# SLAYER_Sensors.net
KiCad netlist of a schematic drawn in Altium Designer
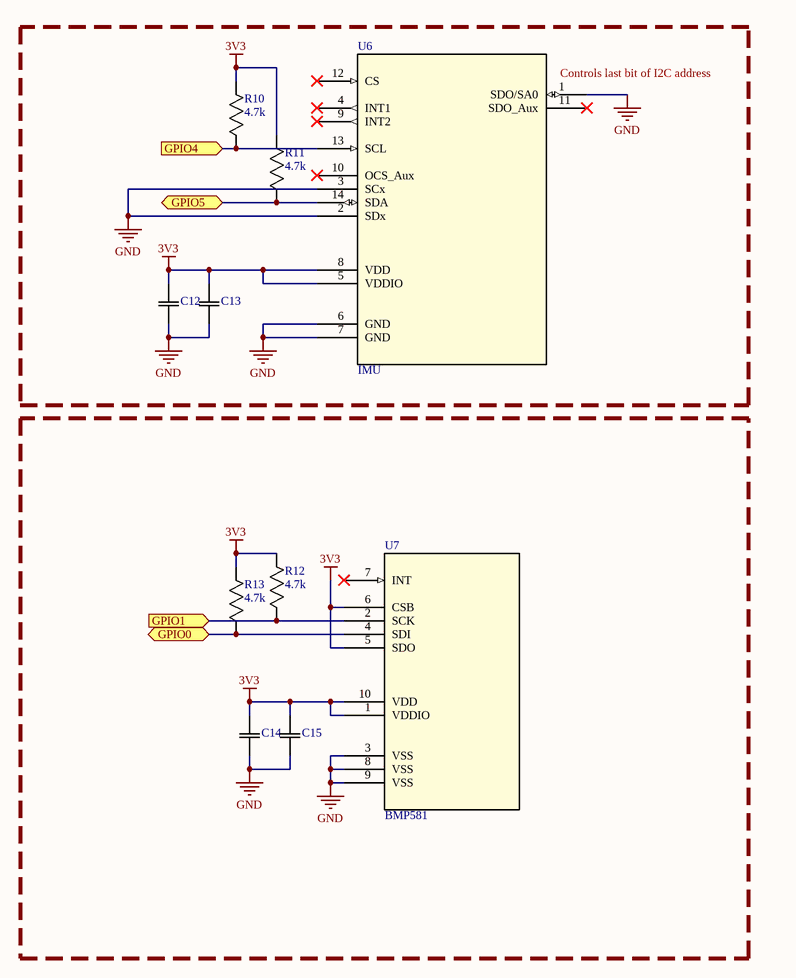
[diagram p0: SLAYER_Sensors.SchDoc]

(export (version "E")
  (design (tool "Eeschema 10.0.6"))
  (components
    (comp (ref "C12")
      (value "CC0603KRX7R9BB104")
      (footprint "0.1uF/50V")
      (fields (field (name "COPYRIGHT") "Copyright (C) 2025 Ultra Librarian. All rights reserved."))
      (libsource (lib "SLAYER_Altium_Sch") (part "0.1uF/50V"))
    )
    (comp (ref "C13")
      (value "CC0603KRX7R9BB104")
      (footprint "0.1uF/50V")
      (fields (field (name "COPYRIGHT") "Copyright (C) 2025 Ultra Librarian. All rights reserved."))
      (libsource (lib "SLAYER_Altium_Sch") (part "0.1uF/50V"))
    )
    (comp (ref "C14")
      (value "CC0603KRX7R9BB104")
      (footprint "0.1uF/50V")
      (fields (field (name "COPYRIGHT") "Copyright (C) 2025 Ultra Librarian. All rights reserved."))
      (libsource (lib "SLAYER_Altium_Sch") (part "0.1uF/50V"))
    )
    (comp (ref "C15")
      (value "CC0603KRX7R9BB104")
      (footprint "0.1uF/50V")
      (fields (field (name "COPYRIGHT") "Copyright (C) 2025 Ultra Librarian. All rights reserved."))
      (libsource (lib "SLAYER_Altium_Sch") (part "0.1uF/50V"))
    )
    (comp (ref "R10")
      (value "4.7k")
      (footprint "4.7k/0.125W")
      (description "CRCW06034K70FKEA")
      (fields (field (name "COPYRIGHT") "Copyright (C) 2025 Ultra Librarian. All rights reserved."))
      (libsource (lib "SLAYER_Altium_Sch") (part "4.7k/0.125W"))
    )
    (comp (ref "R11")
      (value "4.7k")
      (footprint "4.7k/0.125W")
      (description "CRCW06034K70FKEA")
      (fields (field (name "COPYRIGHT") "Copyright (C) 2025 Ultra Librarian. All rights reserved."))
      (libsource (lib "SLAYER_Altium_Sch") (part "4.7k/0.125W"))
    )
    (comp (ref "R12")
      (value "4.7k")
      (footprint "4.7k/0.125W")
      (description "CRCW06034K70FKEA")
      (fields (field (name "COPYRIGHT") "Copyright (C) 2025 Ultra Librarian. All rights reserved."))
      (libsource (lib "SLAYER_Altium_Sch") (part "4.7k/0.125W"))
    )
    (comp (ref "R13")
      (value "4.7k")
      (footprint "4.7k/0.125W")
      (description "CRCW06034K70FKEA")
      (fields (field (name "COPYRIGHT") "Copyright (C) 2025 Ultra Librarian. All rights reserved."))
      (libsource (lib "SLAYER_Altium_Sch") (part "4.7k/0.125W"))
    )
    (comp (ref "U6")
      (value "IMU")
      (footprint "IMU")
      (description "LSM6DSMTR")
      (fields (field (name "COPYRIGHT") "Copyright (C) 2026 Ultra Librarian. All rights reserved."))
      (libsource (lib "SLAYER_Altium_Sch") (part "IMU"))
    )
    (comp (ref "U7")
      (value "BMP581")
      (footprint "BMP581")
      (fields (field (name "COPYRIGHT") "Copyright (C) 2026 Ultra Librarian. All rights reserved."))
      (libsource (lib "SLAYER_Altium_Sch") (part "BMP581"))
    )
  )
  (nets
    (net (code "1") (name "/GPIO0") (class "Default")
      (node (ref "R13") (pin "2") (pinfunction "2_2") (pintype "passive"))
      (node (ref "U7") (pin "4") (pinfunction "SDI_4") (pintype "passive"))
    )
    (net (code "2") (name "/GPIO1") (class "Default")
      (node (ref "R12") (pin "2") (pinfunction "2_2") (pintype "passive"))
      (node (ref "U7") (pin "2") (pinfunction "SCK_2") (pintype "passive"))
    )
    (net (code "3") (name "/GPIO4") (class "Default")
      (node (ref "R10") (pin "2") (pinfunction "2_2") (pintype "passive"))
      (node (ref "U6") (pin "13") (pinfunction "SCL_13") (pintype "input"))
    )
    (net (code "4") (name "/GPIO5") (class "Default")
      (node (ref "R11") (pin "2") (pinfunction "2_2") (pintype "passive"))
      (node (ref "U6") (pin "14") (pinfunction "SDA_14") (pintype "bidirectional"))
    )
    (net (code "5") (name "3V3") (class "Default")
      (node (ref "C12") (pin "2") (pinfunction "2_2") (pintype "passive"))
      (node (ref "C13") (pin "2") (pinfunction "2_2") (pintype "passive"))
      (node (ref "C14") (pin "2") (pinfunction "2_2") (pintype "passive"))
      (node (ref "C15") (pin "2") (pinfunction "2_2") (pintype "passive"))
      (node (ref "R10") (pin "1") (pinfunction "1_1") (pintype "passive"))
      (node (ref "R11") (pin "1") (pinfunction "1_1") (pintype "passive"))
      (node (ref "R12") (pin "1") (pinfunction "1_1") (pintype "passive"))
      (node (ref "R13") (pin "1") (pinfunction "1_1") (pintype "passive"))
      (node (ref "U6") (pin "5") (pinfunction "VDDIO_5") (pintype "power_in"))
      (node (ref "U6") (pin "8") (pinfunction "VDD_8") (pintype "power_in"))
      (node (ref "U7") (pin "1") (pinfunction "VDDIO_1") (pintype "power_in"))
      (node (ref "U7") (pin "10") (pinfunction "VDD_10") (pintype "power_in"))
      (node (ref "U7") (pin "5") (pinfunction "SDO_5") (pintype "passive"))
      (node (ref "U7") (pin "6") (pinfunction "CSB_6") (pintype "passive"))
    )
    (net (code "6") (name "GND") (class "Default")
      (node (ref "C12") (pin "1") (pinfunction "1_1") (pintype "passive"))
      (node (ref "C13") (pin "1") (pinfunction "1_1") (pintype "passive"))
      (node (ref "C14") (pin "1") (pinfunction "1_1") (pintype "passive"))
      (node (ref "C15") (pin "1") (pinfunction "1_1") (pintype "passive"))
      (node (ref "U6") (pin "1") (pinfunction "SDO/SA0_1") (pintype "bidirectional"))
      (node (ref "U6") (pin "2") (pinfunction "SDx_2") (pintype "passive"))
      (node (ref "U6") (pin "3") (pinfunction "SCx_3") (pintype "passive"))
      (node (ref "U6") (pin "6") (pinfunction "GND_6") (pintype "power_in"))
      (node (ref "U6") (pin "7") (pinfunction "GND_7") (pintype "power_in"))
      (node (ref "U7") (pin "3") (pinfunction "VSS_3") (pintype "power_in"))
      (node (ref "U7") (pin "8") (pinfunction "VSS_8") (pintype "power_in"))
      (node (ref "U7") (pin "9") (pinfunction "VSS_9") (pintype "power_in"))
    )
    (net (code "7") (name "unconnected-(U6-CS-Pad12)") (class "Default")
      (node (ref "U6") (pin "12") (pinfunction "CS_12") (pintype "input+no_connect"))
    )
    (net (code "8") (name "unconnected-(U6-INT1-Pad4)") (class "Default")
      (node (ref "U6") (pin "4") (pinfunction "INT1_4") (pintype "output+no_connect"))
    )
    (net (code "9") (name "unconnected-(U6-INT2-Pad9)") (class "Default")
      (node (ref "U6") (pin "9") (pinfunction "INT2_9") (pintype "output+no_connect"))
    )
    (net (code "10") (name "unconnected-(U6-OCS_Aux-Pad10)") (class "Default")
      (node (ref "U6") (pin "10") (pinfunction "OCS_Aux_10") (pintype "passive+no_connect"))
    )
    (net (code "11") (name "unconnected-(U6-SDO_Aux-Pad11)") (class "Default")
      (node (ref "U6") (pin "11") (pinfunction "SDO_Aux_11") (pintype "passive+no_connect"))
    )
    (net (code "12") (name "unconnected-(U7-INT-Pad7)") (class "Default")
      (node (ref "U7") (pin "7") (pinfunction "INT_7") (pintype "input+no_connect"))
    )
  )
)
